# Pi_MCU_shield_2.net
KiCad netlist of a schematic drawn in EAGLE
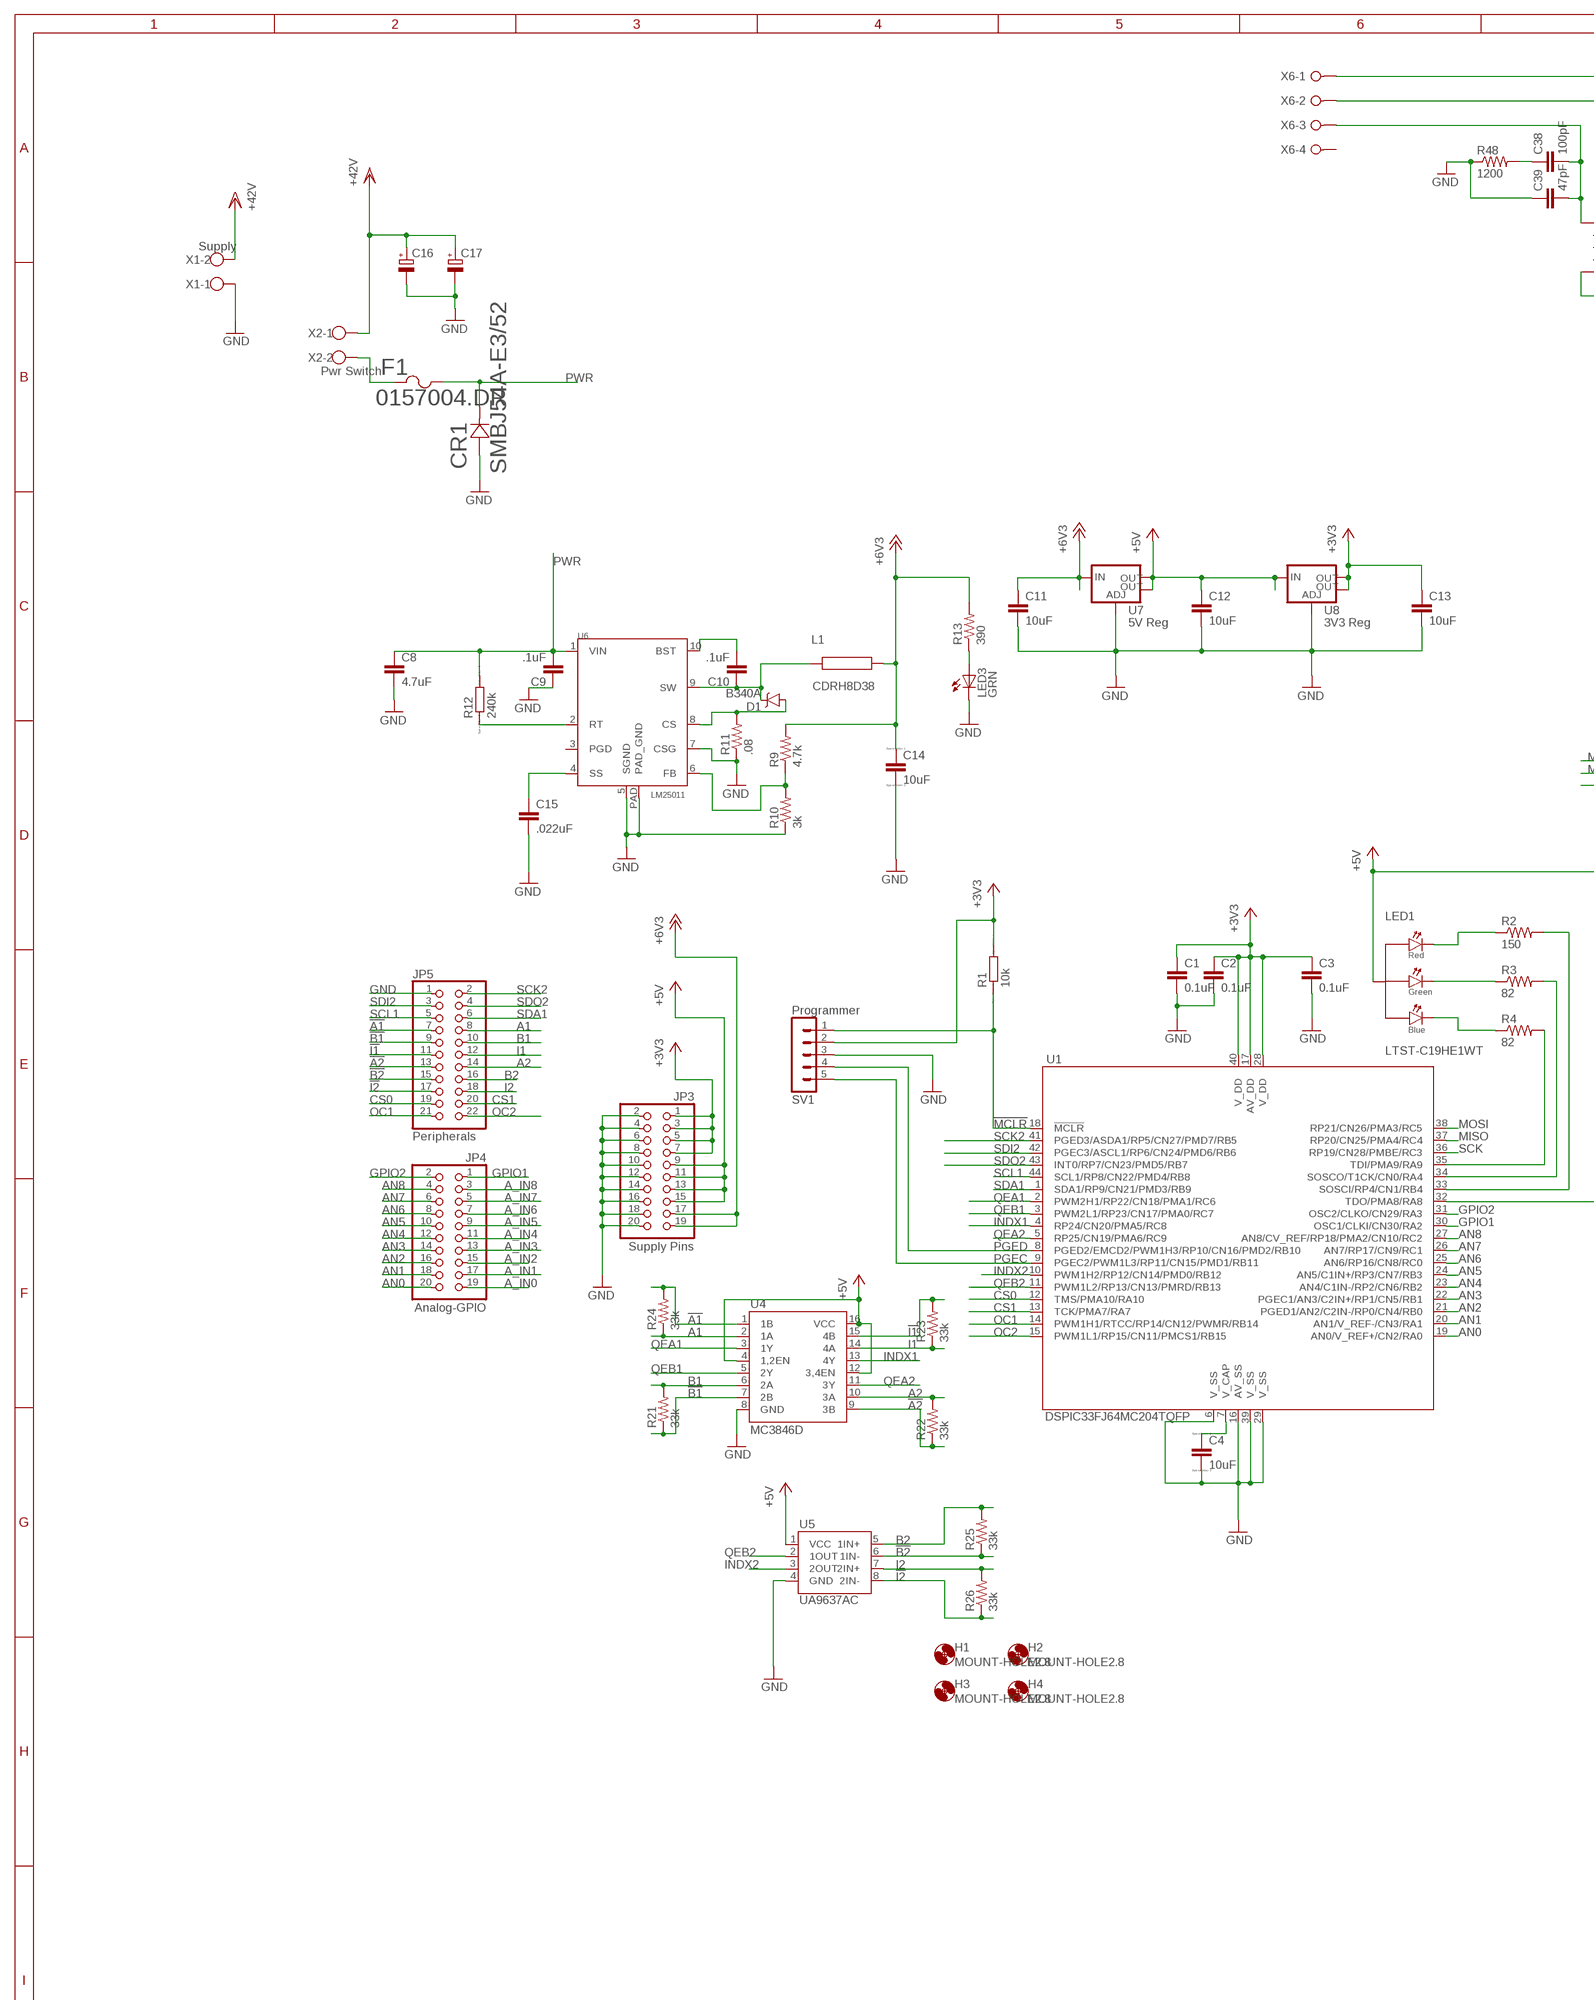
[diagram p0: schematic, sheet 1, part 1 of 2]
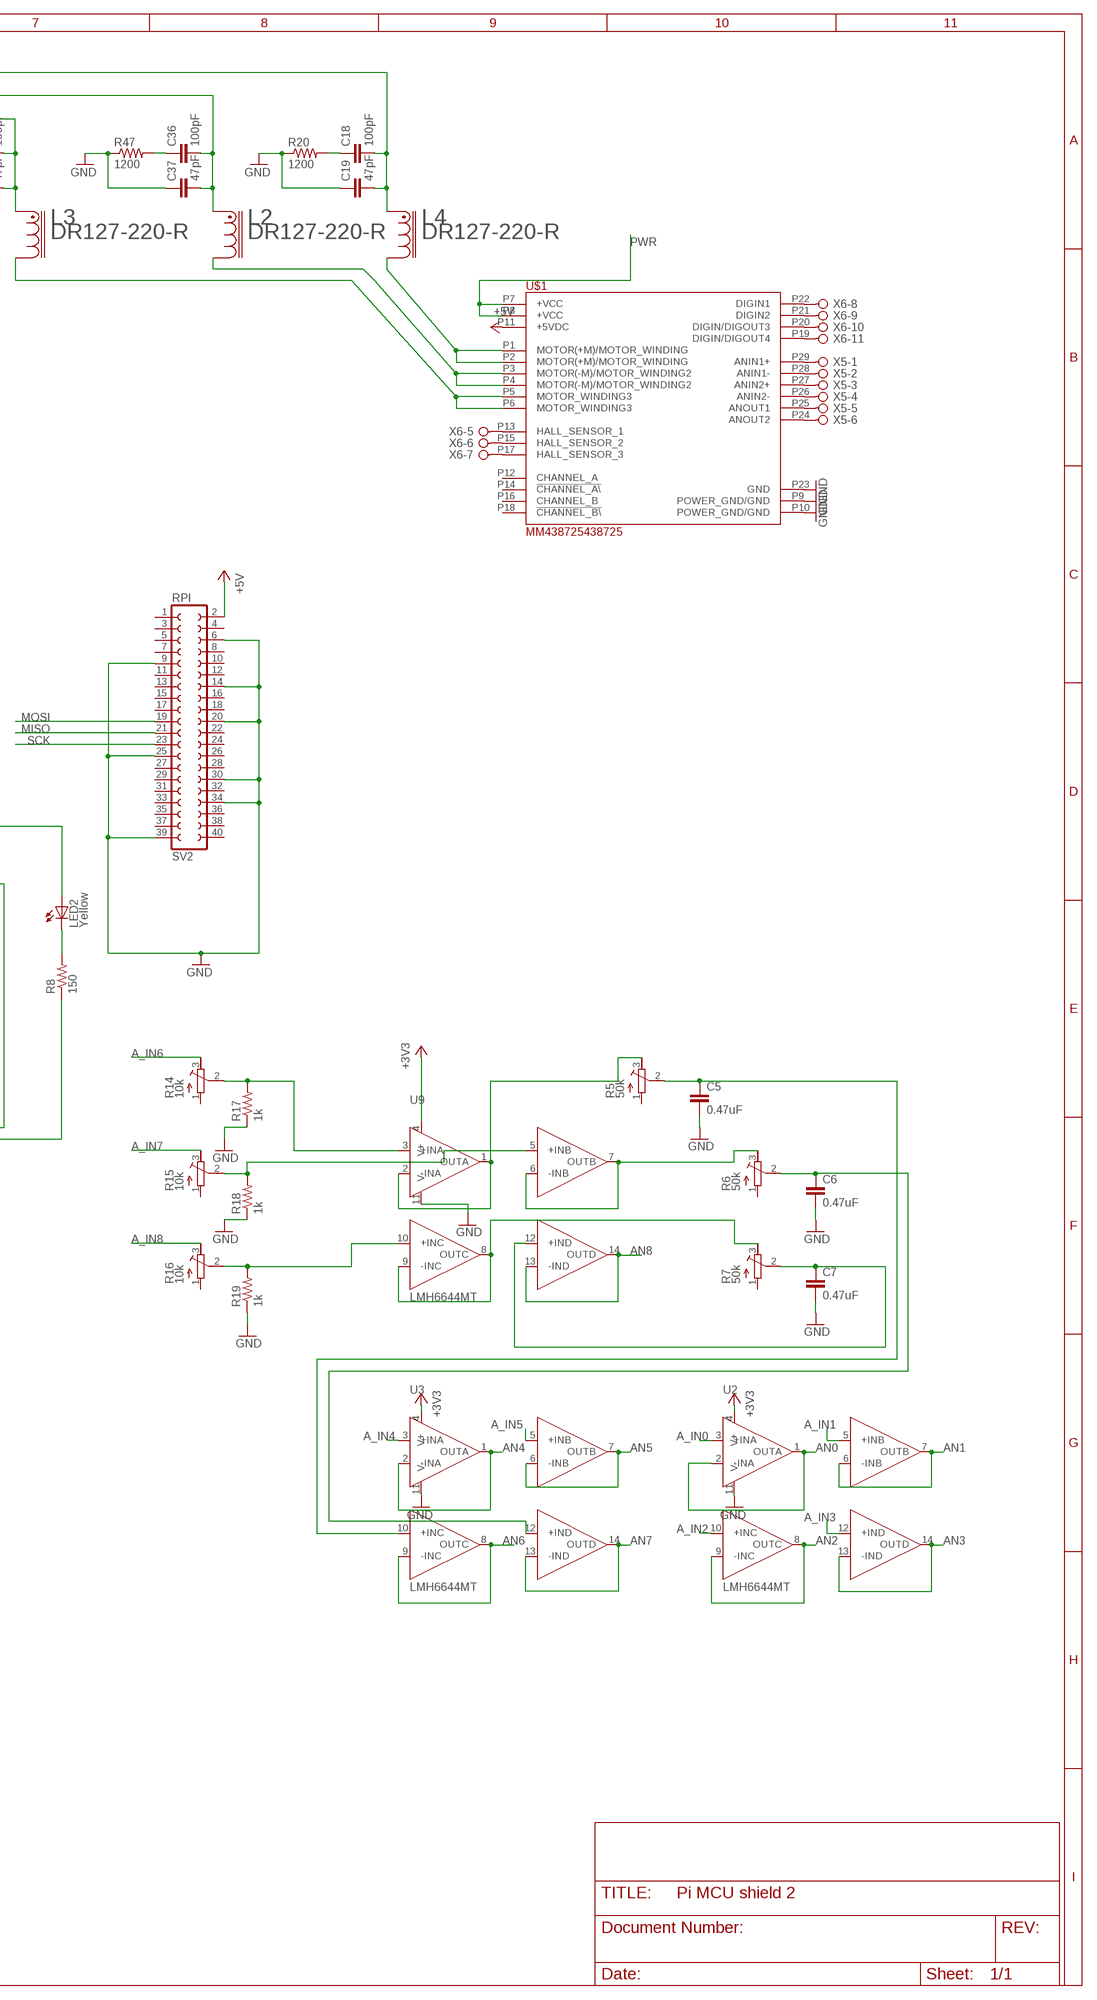
[diagram p1: schematic, sheet 1, part 2 of 2]

(export (version "E")
  (design (tool "Eeschema 10.0.6"))
  (components
    (comp (ref "C1")
      (value "0.1uF")
      (footprint "eagle-import:C0603")
      (libsource (lib "eagle-import") (part "C-EUC0603"))
    )
    (comp (ref "C2")
      (value "0.1uF")
      (footprint "eagle-import:C0603")
      (libsource (lib "eagle-import") (part "C-EUC0603"))
    )
    (comp (ref "C3")
      (value "0.1uF")
      (footprint "eagle-import:C0603")
      (libsource (lib "eagle-import") (part "C-EUC0603"))
    )
    (comp (ref "C4")
      (value "10uF")
      (footprint "eagle-import:C1206")
      (libsource (lib "eagle-import") (part "CC1206"))
    )
    (comp (ref "C5")
      (value "0.47uF")
      (footprint "eagle-import:C0603")
      (libsource (lib "eagle-import") (part "C-EUC0603"))
    )
    (comp (ref "C6")
      (value "0.47uF")
      (footprint "eagle-import:C0603")
      (libsource (lib "eagle-import") (part "C-EUC0603"))
    )
    (comp (ref "C7")
      (value "0.47uF")
      (footprint "eagle-import:C0603")
      (libsource (lib "eagle-import") (part "C-EUC0603"))
    )
    (comp (ref "C8")
      (value "4.7uF")
      (footprint "eagle-import:C1210")
      (libsource (lib "eagle-import") (part "C-EUC1210"))
    )
    (comp (ref "C9")
      (value ".1uF")
      (footprint "eagle-import:0603-CAP")
      (libsource (lib "eagle-import") (part "CAP0603-CAP"))
    )
    (comp (ref "C10")
      (value ".1uF")
      (footprint "eagle-import:0603-CAP")
      (libsource (lib "eagle-import") (part "CAP0603-CAP"))
    )
    (comp (ref "C11")
      (value "10uF")
      (footprint "eagle-import:C0805")
      (libsource (lib "eagle-import") (part "C-EUC0805"))
    )
    (comp (ref "C12")
      (value "10uF")
      (footprint "eagle-import:C0805")
      (libsource (lib "eagle-import") (part "C-EUC0805"))
    )
    (comp (ref "C13")
      (value "10uF")
      (footprint "eagle-import:C0805")
      (libsource (lib "eagle-import") (part "C-EUC0805"))
    )
    (comp (ref "C14")
      (value "10uF")
      (footprint "eagle-import:C1206")
      (libsource (lib "eagle-import") (part "CC1206"))
    )
    (comp (ref "C15")
      (value ".022uF")
      (footprint "eagle-import:0603-CAP")
      (libsource (lib "eagle-import") (part "CAP0603-CAP"))
    )
    (comp (ref "C16")
      (value "CPOL-EUE5-13")
      (footprint "eagle-import:E5-13")
      (libsource (lib "eagle-import") (part "CPOL-EUE5-13"))
    )
    (comp (ref "C17")
      (value "CPOL-EUE5-13")
      (footprint "eagle-import:E5-13")
      (libsource (lib "eagle-import") (part "CPOL-EUE5-13"))
    )
    (comp (ref "C18")
      (value "100pF")
      (footprint "eagle-import:0603-CAP")
      (libsource (lib "eagle-import") (part "CAP0603-CAP"))
    )
    (comp (ref "C19")
      (value "47pF")
      (footprint "eagle-import:0603-CAP")
      (libsource (lib "eagle-import") (part "CAP0603-CAP"))
    )
    (comp (ref "C36")
      (value "100pF")
      (footprint "eagle-import:0603-CAP")
      (libsource (lib "eagle-import") (part "CAP0603-CAP"))
    )
    (comp (ref "C37")
      (value "47pF")
      (footprint "eagle-import:0603-CAP")
      (libsource (lib "eagle-import") (part "CAP0603-CAP"))
    )
    (comp (ref "C38")
      (value "100pF")
      (footprint "eagle-import:0603-CAP")
      (libsource (lib "eagle-import") (part "CAP0603-CAP"))
    )
    (comp (ref "C39")
      (value "47pF")
      (footprint "eagle-import:0603-CAP")
      (libsource (lib "eagle-import") (part "CAP0603-CAP"))
    )
    (comp (ref "CR1")
      (value "SMBJ54A-E3/52")
      (footprint "eagle-import:DIODE_DO-214AC")
      (fields (field (name "MANUFACTURER_PART_NUMBER") "SMBJ54AE352"))
      (libsource (lib "eagle-import") (part "SMBJ54A-E3/52"))
    )
    (comp (ref "D1")
      (value "B340A")
      (footprint "eagle-import:SMA-DIODE")
      (libsource (lib "eagle-import") (part "DIODE-SCHOTTKY-B340A"))
    )
    (comp (ref "F1")
      (value "0157004.DR")
      (footprint "eagle-import:0157SERIES")
      (libsource (lib "eagle-import") (part "0157004.DR"))
    )
    (comp (ref "H1")
      (value "MOUNT-HOLE2.8")
      (footprint "eagle-import:2,8")
      (libsource (lib "eagle-import") (part "MOUNT-HOLE2.8"))
    )
    (comp (ref "H2")
      (value "MOUNT-HOLE2.8")
      (footprint "eagle-import:2,8")
      (libsource (lib "eagle-import") (part "MOUNT-HOLE2.8"))
    )
    (comp (ref "H3")
      (value "MOUNT-HOLE2.8")
      (footprint "eagle-import:2,8")
      (libsource (lib "eagle-import") (part "MOUNT-HOLE2.8"))
    )
    (comp (ref "H4")
      (value "MOUNT-HOLE2.8")
      (footprint "eagle-import:2,8")
      (libsource (lib "eagle-import") (part "MOUNT-HOLE2.8"))
    )
    (comp (ref "JP3")
      (value "Supply Pins")
      (footprint "eagle-import:2X10")
      (libsource (lib "eagle-import") (part "PINHD-2X10"))
    )
    (comp (ref "JP4")
      (value "Analog-GPIO")
      (footprint "eagle-import:2X10")
      (libsource (lib "eagle-import") (part "PINHD-2X10"))
    )
    (comp (ref "JP5")
      (value "Peripherals")
      (footprint "eagle-import:2X11")
      (libsource (lib "eagle-import") (part "PINHD-2X11"))
    )
    (comp (ref "L1")
      (value "CDRH8D38")
      (footprint "eagle-import:CDRH8D38")
      (libsource (lib "eagle-import") (part "CDRH8D38"))
    )
    (comp (ref "L2")
      (value "DR127-220-R")
      (footprint "eagle-import:DR127")
      (fields (field (name "MANUFACTURER_PART_NUMBER") "DR127220R"))
      (libsource (lib "eagle-import") (part "DR127-220-R"))
    )
    (comp (ref "L3")
      (value "DR127-220-R")
      (footprint "eagle-import:DR127")
      (fields (field (name "MANUFACTURER_PART_NUMBER") "DR127220R"))
      (libsource (lib "eagle-import") (part "DR127-220-R"))
    )
    (comp (ref "L4")
      (value "DR127-220-R")
      (footprint "eagle-import:DR127")
      (fields (field (name "MANUFACTURER_PART_NUMBER") "DR127220R"))
      (libsource (lib "eagle-import") (part "DR127-220-R"))
    )
    (comp (ref "LED1")
      (value "LTST-C19HE1WT")
      (footprint "eagle-import:0606")
      (libsource (lib "eagle-import") (part "LTST-C19HE1WT"))
    )
    (comp (ref "LED2")
      (value "Yellow")
      (footprint "eagle-import:SML0603")
      (libsource (lib "eagle-import") (part "LEDSML0603"))
    )
    (comp (ref "LED3")
      (value "GRN")
      (footprint "eagle-import:CHIP-LED0805")
      (libsource (lib "eagle-import") (part "LEDCHIP-LED0805"))
    )
    (comp (ref "R1")
      (value "10k")
      (footprint "eagle-import:R0805")
      (libsource (lib "eagle-import") (part "R"))
    )
    (comp (ref "R2")
      (value "150")
      (footprint "eagle-import:R0603")
      (libsource (lib "eagle-import") (part "R-US_R0603"))
    )
    (comp (ref "R3")
      (value "82")
      (footprint "eagle-import:R0603")
      (libsource (lib "eagle-import") (part "R-US_R0603"))
    )
    (comp (ref "R4")
      (value "82")
      (footprint "eagle-import:R0603")
      (libsource (lib "eagle-import") (part "R-US_R0603"))
    )
    (comp (ref "R5")
      (value "50k")
      (footprint "eagle-import:RTRIM3224J")
      (libsource (lib "eagle-import") (part "R-TRIMM3224J"))
    )
    (comp (ref "R6")
      (value "50k")
      (footprint "eagle-import:RTRIM3224J")
      (libsource (lib "eagle-import") (part "R-TRIMM3224J"))
    )
    (comp (ref "R7")
      (value "50k")
      (footprint "eagle-import:RTRIM3224J")
      (libsource (lib "eagle-import") (part "R-TRIMM3224J"))
    )
    (comp (ref "R8")
      (value "150")
      (footprint "eagle-import:R0603")
      (libsource (lib "eagle-import") (part "R-US_R0603"))
    )
    (comp (ref "R9")
      (value "4.7k")
      (footprint "eagle-import:0603-RES")
      (libsource (lib "eagle-import") (part "RESISTOR0603-RES"))
    )
    (comp (ref "R10")
      (value "3k")
      (footprint "eagle-import:0603-RES")
      (libsource (lib "eagle-import") (part "RESISTOR0603-RES"))
    )
    (comp (ref "R11")
      (value ".08")
      (footprint "eagle-import:0603-RES")
      (libsource (lib "eagle-import") (part "RESISTOR0603-RES"))
    )
    (comp (ref "R12")
      (value "240k")
      (footprint "eagle-import:R0805")
      (libsource (lib "eagle-import") (part "R"))
    )
    (comp (ref "R13")
      (value "390")
      (footprint "eagle-import:0603-RES")
      (libsource (lib "eagle-import") (part "RESISTOR0603-RES"))
    )
    (comp (ref "R14")
      (value "10k")
      (footprint "eagle-import:RTRIM3224J")
      (libsource (lib "eagle-import") (part "R-TRIMM3224J"))
    )
    (comp (ref "R15")
      (value "10k")
      (footprint "eagle-import:RTRIM3224J")
      (libsource (lib "eagle-import") (part "R-TRIMM3224J"))
    )
    (comp (ref "R16")
      (value "10k")
      (footprint "eagle-import:RTRIM3224J")
      (libsource (lib "eagle-import") (part "R-TRIMM3224J"))
    )
    (comp (ref "R17")
      (value "1k")
      (footprint "eagle-import:R0603")
      (libsource (lib "eagle-import") (part "R-US_R0603"))
    )
    (comp (ref "R18")
      (value "1k")
      (footprint "eagle-import:R0603")
      (libsource (lib "eagle-import") (part "R-US_R0603"))
    )
    (comp (ref "R19")
      (value "1k")
      (footprint "eagle-import:R0603")
      (libsource (lib "eagle-import") (part "R-US_R0603"))
    )
    (comp (ref "R20")
      (value "1200")
      (footprint "eagle-import:R0603")
      (libsource (lib "eagle-import") (part "R-US_R0603"))
    )
    (comp (ref "R21")
      (value "33k")
      (footprint "eagle-import:R0603")
      (libsource (lib "eagle-import") (part "R-US_R0603"))
    )
    (comp (ref "R22")
      (value "33k")
      (footprint "eagle-import:R0603")
      (libsource (lib "eagle-import") (part "R-US_R0603"))
    )
    (comp (ref "R23")
      (value "33k")
      (footprint "eagle-import:R0603")
      (libsource (lib "eagle-import") (part "R-US_R0603"))
    )
    (comp (ref "R24")
      (value "33k")
      (footprint "eagle-import:R0603")
      (libsource (lib "eagle-import") (part "R-US_R0603"))
    )
    (comp (ref "R25")
      (value "33k")
      (footprint "eagle-import:R0603")
      (libsource (lib "eagle-import") (part "R-US_R0603"))
    )
    (comp (ref "R26")
      (value "33k")
      (footprint "eagle-import:R0603")
      (libsource (lib "eagle-import") (part "R-US_R0603"))
    )
    (comp (ref "R47")
      (value "1200")
      (footprint "eagle-import:R0603")
      (libsource (lib "eagle-import") (part "R-US_R0603"))
    )
    (comp (ref "R48")
      (value "1200")
      (footprint "eagle-import:R0603")
      (libsource (lib "eagle-import") (part "R-US_R0603"))
    )
    (comp (ref "SV1")
      (value "Programmer")
      (footprint "eagle-import:MA05-1")
      (libsource (lib "eagle-import") (part "MA05-1"))
    )
    (comp (ref "SV2")
      (value "RPI")
      (footprint "eagle-import:FE20-2")
      (libsource (lib "eagle-import") (part "FE20-2"))
    )
    (comp (ref "U$1")
      (value "MM438725438725")
      (footprint "eagle-import:MAX_MOT_438725")
      (libsource (lib "eagle-import") (part "MM438725438725"))
    )
    (comp (ref "U1")
      (value "DSPIC33FJ64MC204TQFP")
      (footprint "eagle-import:TQFP44")
      (libsource (lib "eagle-import") (part "DSPIC33FJ64MC204TQFP"))
    )
    (comp (ref "U2")
      (value "LMH6644MT")
      (footprint "eagle-import:TSSOP14")
      (libsource (lib "eagle-import") (part "LMH6644MT"))
    )
    (comp (ref "U3")
      (value "LMH6644MT")
      (footprint "eagle-import:TSSOP14")
      (libsource (lib "eagle-import") (part "LMH6644MT"))
    )
    (comp (ref "U4")
      (value "MC3846D")
      (footprint "eagle-import:SO-16")
      (libsource (lib "eagle-import") (part "MC3846D"))
    )
    (comp (ref "U5")
      (value "UA9637AC")
      (footprint "eagle-import:SO-08")
      (libsource (lib "eagle-import") (part "UA9637AC"))
    )
    (comp (ref "U6")
      (value "LM25011")
      (footprint "eagle-import:HVSS0P-10")
      (libsource (lib "eagle-import") (part "LM25011"))
    )
    (comp (ref "U7")
      (value "5V Reg")
      (footprint "eagle-import:SOT223")
      (libsource (lib "eagle-import") (part "V_REG_LM1117SOT223"))
    )
    (comp (ref "U8")
      (value "3V3 Reg")
      (footprint "eagle-import:SOT223")
      (libsource (lib "eagle-import") (part "V_REG_LM1117SOT223"))
    )
    (comp (ref "U9")
      (value "LMH6644MT")
      (footprint "eagle-import:TSSOP14")
      (libsource (lib "eagle-import") (part "LMH6644MT"))
    )
    (comp (ref "X1")
      (value "Supply")
      (footprint "eagle-import:W237-102")
      (fields (field (name "MPN") "237-102"))
      (libsource (lib "eagle-import") (part "W237-102"))
    )
    (comp (ref "X2")
      (value "Pwr Switch")
      (footprint "eagle-import:W237-102")
      (fields (field (name "MPN") "237-102"))
      (libsource (lib "eagle-import") (part "W237-102"))
    )
    (comp (ref "X5")
      (value "W237-06P")
      (footprint "eagle-import:W237-6P")
      (libsource (lib "eagle-import") (part "W237-06P"))
    )
    (comp (ref "X6")
      (value "W237-11P")
      (footprint "eagle-import:W237-11P")
      (libsource (lib "eagle-import") (part "W237-11P"))
    )
  )
  (nets
    (net (code "1") (name "+3V3") (class "Default")
      (node (ref "C1") (pin "1") (pinfunction "1_1") (pintype "passive"))
      (node (ref "C13") (pin "1") (pinfunction "1_1") (pintype "passive"))
      (node (ref "C2") (pin "1") (pinfunction "1_1") (pintype "passive"))
      (node (ref "C3") (pin "1") (pinfunction "1_1") (pintype "passive"))
      (node (ref "JP3") (pin "1") (pinfunction "1_1") (pintype "passive"))
      (node (ref "JP3") (pin "3") (pinfunction "3_3") (pintype "passive"))
      (node (ref "JP3") (pin "5") (pinfunction "5_5") (pintype "passive"))
      (node (ref "JP3") (pin "7") (pinfunction "7_7") (pintype "passive"))
      (node (ref "R1") (pin "2") (pinfunction "2_2") (pintype "passive"))
      (node (ref "SV1") (pin "2") (pinfunction "2_2") (pintype "passive"))
      (node (ref "U1") (pin "17") (pinfunction "AV_DD_17") (pintype "power_in"))
      (node (ref "U1") (pin "28") (pinfunction "V_DD_28") (pintype "power_in"))
      (node (ref "U1") (pin "40") (pinfunction "V_DD_40") (pintype "power_in"))
      (node (ref "U2") (pin "4") (pinfunction "V+_4") (pintype "bidirectional"))
      (node (ref "U3") (pin "4") (pinfunction "V+_4") (pintype "bidirectional"))
      (node (ref "U8") (pin "2") (pinfunction "OUT_2") (pintype "output"))
      (node (ref "U8") (pin "4") (pinfunction "OUT_4") (pintype "output"))
      (node (ref "U9") (pin "4") (pinfunction "V+_4") (pintype "bidirectional"))
    )
    (net (code "2") (name "+5V") (class "Default")
      (node (ref "C12") (pin "1") (pinfunction "1_1") (pintype "passive"))
      (node (ref "JP3") (pin "11") (pinfunction "11_11") (pintype "passive"))
      (node (ref "JP3") (pin "13") (pinfunction "13_13") (pintype "passive"))
      (node (ref "JP3") (pin "15") (pinfunction "15_15") (pintype "passive"))
      (node (ref "JP3") (pin "9") (pinfunction "9_9") (pintype "passive"))
      (node (ref "LED1") (pin "4") (pinfunction "ANODE_4") (pintype "passive"))
      (node (ref "LED2") (pin "A") (pinfunction "A_A") (pintype "passive"))
      (node (ref "SV2") (pin "2") (pinfunction "2_2") (pintype "passive"))
      (node (ref "U$1") (pin "P11") (pinfunction "+5VDC_P11") (pintype "power_in"))
      (node (ref "U4") (pin "12") (pinfunction "3,4EN_12") (pintype "bidirectional"))
      (node (ref "U4") (pin "16") (pinfunction "VCC_16") (pintype "power_in"))
      (node (ref "U4") (pin "4") (pinfunction "1,2EN_4") (pintype "input"))
      (node (ref "U5") (pin "1") (pinfunction "VCC_1") (pintype "power_in"))
      (node (ref "U7") (pin "2") (pinfunction "OUT_2") (pintype "output"))
      (node (ref "U7") (pin "4") (pinfunction "OUT_4") (pintype "output"))
      (node (ref "U8") (pin "3") (pinfunction "IN_3") (pintype "input"))
    )
    (net (code "3") (name "+6V3") (class "Default")
      (node (ref "C11") (pin "1") (pinfunction "1_1") (pintype "passive"))
      (node (ref "C14") (pin "1") (pinfunction "1_1") (pintype "passive"))
      (node (ref "JP3") (pin "17") (pinfunction "17_17") (pintype "passive"))
      (node (ref "JP3") (pin "19") (pinfunction "19_19") (pintype "passive"))
      (node (ref "L1") (pin "P$2") (pinfunction "2_P$2") (pintype "passive"))
      (node (ref "R13") (pin "2") (pinfunction "2_2") (pintype "passive"))
      (node (ref "R9") (pin "2") (pinfunction "2_2") (pintype "passive"))
      (node (ref "U7") (pin "3") (pinfunction "IN_3") (pintype "input"))
    )
    (net (code "4") (name "+42V") (class "Default")
      (node (ref "C16") (pin "+") (pinfunction "+_+") (pintype "passive"))
      (node (ref "C17") (pin "+") (pinfunction "+_+") (pintype "passive"))
      (node (ref "X1") (pin "2") (pinfunction "KL_2") (pintype "passive"))
      (node (ref "X2") (pin "1") (pinfunction "KL_1") (pintype "passive"))
    )
    (net (code "5") (name "/A1") (class "Default")
      (node (ref "JP5") (pin "8") (pinfunction "8_8") (pintype "passive"))
      (node (ref "R24") (pin "1") (pinfunction "1_1") (pintype "passive"))
      (node (ref "U4") (pin "2") (pinfunction "1A_2") (pintype "input"))
    )
    (net (code "6") (name "/A2") (class "Default")
      (node (ref "JP5") (pin "14") (pinfunction "14_14") (pintype "passive"))
      (node (ref "R22") (pin "2") (pinfunction "2_2") (pintype "passive"))
      (node (ref "U4") (pin "10") (pinfunction "3A_10") (pintype "input"))
    )
    (net (code "7") (name "/AN0") (class "Default")
      (node (ref "JP4") (pin "20") (pinfunction "20_20") (pintype "passive"))
      (node (ref "U1") (pin "19") (pinfunction "AN0/V_REF+/CN2/RA0_19") (pintype "bidirectional"))
      (node (ref "U2") (pin "1") (pinfunction "OUTA_1") (pintype "bidirectional"))
      (node (ref "U2") (pin "2") (pinfunction "-INA_2") (pintype "bidirectional"))
    )
    (net (code "8") (name "/AN1") (class "Default")
      (node (ref "JP4") (pin "18") (pinfunction "18_18") (pintype "passive"))
      (node (ref "U1") (pin "20") (pinfunction "AN1/V_REF-/CN3/RA1_20") (pintype "bidirectional"))
      (node (ref "U2") (pin "6") (pinfunction "-INB_6") (pintype "bidirectional"))
      (node (ref "U2") (pin "7") (pinfunction "OUTB_7") (pintype "bidirectional"))
    )
    (net (code "9") (name "/AN2") (class "Default")
      (node (ref "JP4") (pin "16") (pinfunction "16_16") (pintype "passive"))
      (node (ref "U1") (pin "21") (pinfunction "PGED1/AN2/C2IN-/RP0/CN4/RB0_21") (pintype "bidirectional"))
      (node (ref "U2") (pin "8") (pinfunction "OUTC_8") (pintype "bidirectional"))
      (node (ref "U2") (pin "9") (pinfunction "-INC_9") (pintype "bidirectional"))
    )
    (net (code "10") (name "/AN3") (class "Default")
      (node (ref "JP4") (pin "14") (pinfunction "14_14") (pintype "passive"))
      (node (ref "U1") (pin "22") (pinfunction "PGEC1/AN3/C2IN+/RP1/CN5/RB1_22") (pintype "bidirectional"))
      (node (ref "U2") (pin "13") (pinfunction "-IND_13") (pintype "bidirectional"))
      (node (ref "U2") (pin "14") (pinfunction "OUTD_14") (pintype "bidirectional"))
    )
    (net (code "11") (name "/AN4") (class "Default")
      (node (ref "JP4") (pin "12") (pinfunction "12_12") (pintype "passive"))
      (node (ref "U1") (pin "23") (pinfunction "AN4/C1IN-/RP2/CN6/RB2_23") (pintype "bidirectional"))
      (node (ref "U3") (pin "1") (pinfunction "OUTA_1") (pintype "bidirectional"))
      (node (ref "U3") (pin "2") (pinfunction "-INA_2") (pintype "bidirectional"))
    )
    (net (code "12") (name "/AN5") (class "Default")
      (node (ref "JP4") (pin "10") (pinfunction "10_10") (pintype "passive"))
      (node (ref "U1") (pin "24") (pinfunction "AN5/C1IN+/RP3/CN7/RB3_24") (pintype "bidirectional"))
      (node (ref "U3") (pin "6") (pinfunction "-INB_6") (pintype "bidirectional"))
      (node (ref "U3") (pin "7") (pinfunction "OUTB_7") (pintype "bidirectional"))
    )
    (net (code "13") (name "/AN6") (class "Default")
      (node (ref "JP4") (pin "8") (pinfunction "8_8") (pintype "passive"))
      (node (ref "U1") (pin "25") (pinfunction "AN6/RP16/CN8/RC0_25") (pintype "bidirectional"))
      (node (ref "U3") (pin "8") (pinfunction "OUTC_8") (pintype "bidirectional"))
      (node (ref "U3") (pin "9") (pinfunction "-INC_9") (pintype "bidirectional"))
    )
    (net (code "14") (name "/AN7") (class "Default")
      (node (ref "JP4") (pin "6") (pinfunction "6_6") (pintype "passive"))
      (node (ref "U1") (pin "26") (pinfunction "AN7/RP17/CN9/RC1_26") (pintype "bidirectional"))
      (node (ref "U3") (pin "13") (pinfunction "-IND_13") (pintype "bidirectional"))
      (node (ref "U3") (pin "14") (pinfunction "OUTD_14") (pintype "bidirectional"))
    )
    (net (code "15") (name "/AN8") (class "Default")
      (node (ref "JP4") (pin "4") (pinfunction "4_4") (pintype "passive"))
      (node (ref "U1") (pin "27") (pinfunction "AN8/CV_REF/RP18/PMA2/CN10/RC2_27") (pintype "bidirectional"))
      (node (ref "U9") (pin "13") (pinfunction "-IND_13") (pintype "bidirectional"))
      (node (ref "U9") (pin "14") (pinfunction "OUTD_14") (pintype "bidirectional"))
    )
    (net (code "16") (name "/A_IN0") (class "Default")
      (node (ref "JP4") (pin "19") (pinfunction "19_19") (pintype "passive"))
      (node (ref "U2") (pin "3") (pinfunction "+INA_3") (pintype "bidirectional"))
    )
    (net (code "17") (name "/A_IN1") (class "Default")
      (node (ref "JP4") (pin "17") (pinfunction "17_17") (pintype "passive"))
      (node (ref "U2") (pin "5") (pinfunction "+INB_5") (pintype "bidirectional"))
    )
    (net (code "18") (name "/A_IN2") (class "Default")
      (node (ref "JP4") (pin "15") (pinfunction "15_15") (pintype "passive"))
      (node (ref "U2") (pin "10") (pinfunction "+INC_10") (pintype "bidirectional"))
    )
    (net (code "19") (name "/A_IN3") (class "Default")
      (node (ref "JP4") (pin "13") (pinfunction "13_13") (pintype "passive"))
      (node (ref "U2") (pin "12") (pinfunction "+IND_12") (pintype "bidirectional"))
    )
    (net (code "20") (name "/A_IN4") (class "Default")
      (node (ref "JP4") (pin "11") (pinfunction "11_11") (pintype "passive"))
      (node (ref "U3") (pin "3") (pinfunction "+INA_3") (pintype "bidirectional"))
    )
    (net (code "21") (name "/A_IN5") (class "Default")
      (node (ref "JP4") (pin "9") (pinfunction "9_9") (pintype "passive"))
      (node (ref "U3") (pin "5") (pinfunction "+INB_5") (pintype "bidirectional"))
    )
    (net (code "22") (name "/A_IN6") (class "Default")
      (node (ref "JP4") (pin "7") (pinfunction "7_7") (pintype "passive"))
      (node (ref "R14") (pin "3") (pinfunction "E_3") (pintype "passive"))
    )
    (net (code "23") (name "/A_IN7") (class "Default")
      (node (ref "JP4") (pin "5") (pinfunction "5_5") (pintype "passive"))
      (node (ref "R15") (pin "3") (pinfunction "E_3") (pintype "passive"))
    )
    (net (code "24") (name "/A_IN8") (class "Default")
      (node (ref "JP4") (pin "3") (pinfunction "3_3") (pintype "passive"))
      (node (ref "R16") (pin "3") (pinfunction "E_3") (pintype "passive"))
    )
    (net (code "25") (name "/B1") (class "Default")
      (node (ref "JP5") (pin "10") (pinfunction "10_10") (pintype "passive"))
      (node (ref "R21") (pin "2") (pinfunction "2_2") (pintype "passive"))
      (node (ref "U4") (pin "6") (pinfunction "2A_6") (pintype "input"))
    )
    (net (code "26") (name "/B2") (class "Default")
      (node (ref "JP5") (pin "16") (pinfunction "16_16") (pintype "passive"))
      (node (ref "R25") (pin "2") (pinfunction "2_2") (pintype "passive"))
      (node (ref "U5") (pin "5") (pinfunction "1IN+_5") (pintype "input"))
    )
    (net (code "27") (name "/CS0") (class "Default")
      (node (ref "JP5") (pin "19") (pinfunction "19_19") (pintype "passive"))
      (node (ref "U1") (pin "12") (pinfunction "TMS/PMA10/RA10_12") (pintype "bidirectional"))
    )
    (net (code "28") (name "/CS1") (class "Default")
      (node (ref "JP5") (pin "20") (pinfunction "20_20") (pintype "passive"))
      (node (ref "U1") (pin "13") (pinfunction "TCK/PMA7/RA7_13") (pintype "bidirectional"))
    )
    (net (code "29") (name "/GPIO1") (class "Default")
      (node (ref "JP4") (pin "1") (pinfunction "1_1") (pintype "passive"))
      (node (ref "U1") (pin "30") (pinfunction "OSC1/CLKI/CN30/RA2_30") (pintype "bidirectional"))
    )
    (net (code "30") (name "/GPIO2") (class "Default")
      (node (ref "JP4") (pin "2") (pinfunction "2_2") (pintype "passive"))
      (node (ref "U1") (pin "31") (pinfunction "OSC2/CLKO/CN29/RA3_31") (pintype "bidirectional"))
    )
    (net (code "31") (name "/I1") (class "Default")
      (node (ref "JP5") (pin "12") (pinfunction "12_12") (pintype "passive"))
      (node (ref "R23") (pin "1") (pinfunction "1_1") (pintype "passive"))
      (node (ref "U4") (pin "14") (pinfunction "4A_14") (pintype "input"))
    )
    (net (code "32") (name "/I2") (class "Default")
      (node (ref "JP5") (pin "18") (pinfunction "18_18") (pintype "passive"))
      (node (ref "R26") (pin "2") (pinfunction "2_2") (pintype "passive"))
      (node (ref "U5") (pin "7") (pinfunction "2IN+_7") (pintype "input"))
    )
    (net (code "33") (name "/INDX1") (class "Default")
      (node (ref "U1") (pin "4") (pinfunction "RP24/CN20/PMA5/RC8_4") (pintype "bidirectional"))
      (node (ref "U4") (pin "13") (pinfunction "4Y_13") (pintype "output"))
    )
    (net (code "34") (name "/INDX2") (class "Default")
      (node (ref "U1") (pin "10") (pinfunction "PWM1H2/RP12/CN14/PMD0/RB12_10") (pintype "bidirectional"))
      (node (ref "U5") (pin "3") (pinfunction "2OUT_3") (pintype "output"))
    )
    (net (code "35") (name "/MISO") (class "Default")
      (node (ref "SV2") (pin "21") (pinfunction "21_21") (pintype "passive"))
      (node (ref "U1") (pin "37") (pinfunction "RP20/CN25/PMA4/RC4_37") (pintype "bidirectional"))
    )
    (net (code "36") (name "/MOSI") (class "Default")
      (node (ref "SV2") (pin "19") (pinfunction "19_19") (pintype "passive"))
      (node (ref "U1") (pin "38") (pinfunction "RP21/CN26/PMA3/RC5_38") (pintype "bidirectional"))
    )
    (net (code "37") (name "/OC1") (class "Default")
      (node (ref "JP5") (pin "21") (pinfunction "21_21") (pintype "passive"))
      (node (ref "U1") (pin "14") (pinfunction "PWM1H1/RTCC/RP14/CN12/PWMR/RB14_14") (pintype "bidirectional"))
    )
    (net (code "38") (name "/OC2") (class "Default")
      (node (ref "JP5") (pin "22") (pinfunction "22_22") (pintype "passive"))
      (node (ref "U1") (pin "15") (pinfunction "PWM1L1/RP15/CN11/PMCS1/RB15_15") (pintype "bidirectional"))
    )
    (net (code "39") (name "/PGEC") (class "Default")
      (node (ref "SV1") (pin "5") (pinfunction "5_5") (pintype "passive"))
      (node (ref "U1") (pin "9") (pinfunction "PGEC2/PWM1L3/RP11/CN15/PMD1/RB11_9") (pintype "bidirectional"))
    )
    (net (code "40") (name "/PGED") (class "Default")
      (node (ref "SV1") (pin "4") (pinfunction "4_4") (pintype "passive"))
      (node (ref "U1") (pin "8") (pinfunction "PGED2/EMCD2/PWM1H3/RP10/CN16/PMD2/RB10_8") (pintype "bidirectional"))
    )
    (net (code "41") (name "/PWR") (class "Default")
      (node (ref "C8") (pin "1") (pinfunction "1_1") (pintype "passive"))
      (node (ref "C9") (pin "2") (pinfunction "2_2") (pintype "passive"))
      (node (ref "CR1") (pin "1") (pinfunction "12_1") (pintype "passive"))
      (node (ref "F1") (pin "2") (pinfunction "2_2") (pintype "passive"))
      (node (ref "R12") (pin "2") (pinfunction "2_2") (pintype "passive"))
      (node (ref "U$1") (pin "P7") (pinfunction "+VCC_P7") (pintype "power_in"))
      (node (ref "U$1") (pin "P8") (pinfunction "+VCC_P8") (pintype "power_in"))
      (node (ref "U6") (pin "1") (pinfunction "VIN_1") (pintype "bidirectional"))
    )
    (net (code "42") (name "/QEA1") (class "Default")
      (node (ref "U1") (pin "2") (pinfunction "PWM2H1/RP22/CN18/PMA1/RC6_2") (pintype "bidirectional"))
      (node (ref "U4") (pin "3") (pinfunction "1Y_3") (pintype "output"))
    )
    (net (code "43") (name "/QEA2") (class "Default")
      (node (ref "U1") (pin "5") (pinfunction "RP25/CN19/PMA6/RC9_5") (pintype "bidirectional"))
      (node (ref "U4") (pin "11") (pinfunction "3Y_11") (pintype "output"))
    )
    (net (code "44") (name "/QEB1") (class "Default")
      (node (ref "U1") (pin "3") (pinfunction "PWM2L1/RP23/CN17/PMA0/RC7_3") (pintype "bidirectional"))
      (node (ref "U4") (pin "5") (pinfunction "2Y_5") (pintype "output"))
    )
    (net (code "45") (name "/QEB2") (class "Default")
      (node (ref "U1") (pin "11") (pinfunction "PWM1L2/RP13/CN13/PMRD/RB13_11") (pintype "bidirectional"))
      (node (ref "U5") (pin "2") (pinfunction "1OUT_2") (pintype "output"))
    )
    (net (code "46") (name "/SCK") (class "Default")
      (node (ref "SV2") (pin "23") (pinfunction "23_23") (pintype "passive"))
      (node (ref "U1") (pin "36") (pinfunction "RP19/CN28/PMBE/RC3_36") (pintype "bidirectional"))
    )
    (net (code "47") (name "/SCK2") (class "Default")
      (node (ref "JP5") (pin "2") (pinfunction "2_2") (pintype "passive"))
      (node (ref "U1") (pin "41") (pinfunction "PGED3/ASDA1/RP5/CN27/PMD7/RB5_41") (pintype "bidirectional"))
    )
    (net (code "48") (name "/SCL1") (class "Default")
      (node (ref "JP5") (pin "5") (pinfunction "5_5") (pintype "passive"))
      (node (ref "U1") (pin "44") (pinfunction "SCL1/RP8/CN22/PMD4/RB8_44") (pintype "bidirectional"))
    )
    (net (code "49") (name "/SDA1") (class "Default")
      (node (ref "JP5") (pin "6") (pinfunction "6_6") (pintype "passive"))
      (node (ref "U1") (pin "1") (pinfunction "SDA1/RP9/CN21/PMD3/RB9_1") (pintype "bidirectional"))
    )
    (net (code "50") (name "/SDI2") (class "Default")
      (node (ref "JP5") (pin "3") (pinfunction "3_3") (pintype "passive"))
      (node (ref "U1") (pin "42") (pinfunction "PGEC3/ASCL1/RP6/CN24/PMD6/RB6_42") (pintype "bidirectional"))
    )
    (net (code "51") (name "/SDO2") (class "Default")
      (node (ref "JP5") (pin "4") (pinfunction "4_4") (pintype "passive"))
      (node (ref "U1") (pin "43") (pinfunction "INT0/RP7/CN23/PMD5/RB7_43") (pintype "bidirectional"))
    )
    (net (code "52") (name "/~{A1}") (class "Default")
      (node (ref "JP5") (pin "7") (pinfunction "7_7") (pintype "passive"))
      (node (ref "R24") (pin "2") (pinfunction "2_2") (pintype "passive"))
      (node (ref "U4") (pin "1") (pinfunction "1B_1") (pintype "input"))
    )
    (net (code "53") (name "/~{A2}") (class "Default")
      (node (ref "JP5") (pin "13") (pinfunction "13_13") (pintype "passive"))
      (node (ref "R22") (pin "1") (pinfunction "1_1") (pintype "passive"))
      (node (ref "U4") (pin "9") (pinfunction "3B_9") (pintype "input"))
    )
    (net (code "54") (name "/~{B1}") (class "Default")
      (node (ref "JP5") (pin "9") (pinfunction "9_9") (pintype "passive"))
      (node (ref "R21") (pin "1") (pinfunction "1_1") (pintype "passive"))
      (node (ref "U4") (pin "7") (pinfunction "2B_7") (pintype "input"))
    )
    (net (code "55") (name "/~{B2}") (class "Default")
      (node (ref "JP5") (pin "15") (pinfunction "15_15") (pintype "passive"))
      (node (ref "R25") (pin "1") (pinfunction "1_1") (pintype "passive"))
      (node (ref "U5") (pin "6") (pinfunction "1IN-_6") (pintype "input"))
    )
    (net (code "56") (name "/~{I1}") (class "Default")
      (node (ref "JP5") (pin "11") (pinfunction "11_11") (pintype "passive"))
      (node (ref "R23") (pin "2") (pinfunction "2_2") (pintype "passive"))
      (node (ref "U4") (pin "15") (pinfunction "4B_15") (pintype "input"))
    )
    (net (code "57") (name "/~{I2}") (class "Default")
      (node (ref "JP5") (pin "17") (pinfunction "17_17") (pintype "passive"))
      (node (ref "R26") (pin "1") (pinfunction "1_1") (pintype "passive"))
      (node (ref "U5") (pin "8") (pinfunction "2IN-_8") (pintype "input"))
    )
    (net (code "58") (name "/~{MCLR}") (class "Default")
      (node (ref "R1") (pin "1") (pinfunction "1_1") (pintype "passive"))
      (node (ref "SV1") (pin "1") (pinfunction "1_1") (pintype "passive"))
      (node (ref "U1") (pin "18") (pinfunction "~{MCLR}_18") (pintype "bidirectional"))
    )
    (net (code "59") (name "GND") (class "Default")
      (node (ref "C1") (pin "2") (pinfunction "2_2") (pintype "passive"))
      (node (ref "C11") (pin "2") (pinfunction "2_2") (pintype "passive"))
      (node (ref "C12") (pin "2") (pinfunction "2_2") (pintype "passive"))
      (node (ref "C13") (pin "2") (pinfunction "2_2") (pintype "passive"))
      (node (ref "C14") (pin "2") (pinfunction "2_2") (pintype "passive"))
      (node (ref "C15") (pin "2") (pinfunction "2_2") (pintype "passive"))
      (node (ref "C16") (pin "-") (pinfunction "-_-") (pintype "passive"))
      (node (ref "C17") (pin "-") (pinfunction "-_-") (pintype "passive"))
      (node (ref "C19") (pin "1") (pinfunction "1_1") (pintype "passive"))
      (node (ref "C2") (pin "2") (pinfunction "2_2") (pintype "passive"))
      (node (ref "C3") (pin "2") (pinfunction "2_2") (pintype "passive"))
      (node (ref "C37") (pin "1") (pinfunction "1_1") (pintype "passive"))
      (node (ref "C39") (pin "1") (pinfunction "1_1") (pintype "passive"))
      (node (ref "C4") (pin "2") (pinfunction "2_2") (pintype "passive"))
      (node (ref "C5") (pin "2") (pinfunction "2_2") (pintype "passive"))
      (node (ref "C6") (pin "2") (pinfunction "2_2") (pintype "passive"))
      (node (ref "C7") (pin "2") (pinfunction "2_2") (pintype "passive"))
      (node (ref "C8") (pin "2") (pinfunction "2_2") (pintype "passive"))
      (node (ref "C9") (pin "1") (pinfunction "1_1") (pintype "passive"))
      (node (ref "CR1") (pin "2") (pinfunction "21_2") (pintype "passive"))
      (node (ref "JP3") (pin "10") (pinfunction "10_10") (pintype "passive"))
      (node (ref "JP3") (pin "12") (pinfunction "12_12") (pintype "passive"))
      (node (ref "JP3") (pin "14") (pinfunction "14_14") (pintype "passive"))
      (node (ref "JP3") (pin "16") (pinfunction "16_16") (pintype "passive"))
      (node (ref "JP3") (pin "18") (pinfunction "18_18") (pintype "passive"))
      (node (ref "JP3") (pin "2") (pinfunction "2_2") (pintype "passive"))
      (node (ref "JP3") (pin "20") (pinfunction "20_20") (pintype "passive"))
      (node (ref "JP3") (pin "4") (pinfunction "4_4") (pintype "passive"))
      (node (ref "JP3") (pin "6") (pinfunction "6_6") (pintype "passive"))
      (node (ref "JP3") (pin "8") (pinfunction "8_8") (pintype "passive"))
      (node (ref "JP5") (pin "1") (pinfunction "1_1") (pintype "passive"))
      (node (ref "LED3") (pin "C") (pinfunction "C_C") (pintype "passive"))
      (node (ref "R10") (pin "1") (pinfunction "1_1") (pintype "passive"))
      (node (ref "R11") (pin "1") (pinfunction "1_1") (pintype "passive"))
      (node (ref "R17") (pin "1") (pinfunction "1_1") (pintype "passive"))
      (node (ref "R18") (pin "1") (pinfunction "1_1") (pintype "passive"))
      (node (ref "R19") (pin "1") (pinfunction "1_1") (pintype "passive"))
      (node (ref "R20") (pin "1") (pinfunction "1_1") (pintype "passive"))
      (node (ref "R47") (pin "1") (pinfunction "1_1") (pintype "passive"))
      (node (ref "R48") (pin "1") (pinfunction "1_1") (pintype "passive"))
      (node (ref "SV1") (pin "3") (pinfunction "3_3") (pintype "passive"))
      (node (ref "SV2") (pin "14") (pinfunction "14_14") (pintype "passive"))
      (node (ref "SV2") (pin "20") (pinfunction "20_20") (pintype "passive"))
      (node (ref "SV2") (pin "25") (pinfunction "25_25") (pintype "passive"))
      (node (ref "SV2") (pin "30") (pinfunction "30_30") (pintype "passive"))
      (node (ref "SV2") (pin "34") (pinfunction "34_34") (pintype "passive"))
      (node (ref "SV2") (pin "39") (pinfunction "39_39") (pintype "passive"))
      (node (ref "SV2") (pin "6") (pinfunction "6_6") (pintype "passive"))
      (node (ref "SV2") (pin "9") (pinfunction "9_9") (pintype "passive"))
      (node (ref "U$1") (pin "P10") (pinfunction "POWER_GND/GND_P10") (pintype "power_in"))
      (node (ref "U$1") (pin "P23") (pinfunction "GND_P23") (pintype "power_in"))
      (node (ref "U$1") (pin "P9") (pinfunction "POWER_GND/GND_P9") (pintype "power_in"))
      (node (ref "U1") (pin "16") (pinfunction "AV_SS_16") (pintype "power_in"))
      (node (ref "U1") (pin "29") (pinfunction "V_SS_29") (pintype "power_in"))
      (node (ref "U1") (pin "39") (pinfunction "V_SS_39") (pintype "power_in"))
      (node (ref "U1") (pin "6") (pinfunction "V_SS_6") (pintype "power_in"))
      (node (ref "U2") (pin "11") (pinfunction "V-_11") (pintype "bidirectional"))
      (node (ref "U3") (pin "11") (pinfunction "V-_11") (pintype "bidirectional"))
      (node (ref "U4") (pin "8") (pinfunction "GND_8") (pintype "power_in"))
      (node (ref "U5") (pin "4") (pinfunction "GND_4") (pintype "power_in"))
      (node (ref "U6") (pin "5") (pinfunction "SGND_5") (pintype "bidirectional"))
      (node (ref "U6") (pin "7") (pinfunction "CSG_7") (pintype "bidirectional"))
      (node (ref "U6") (pin "PAD") (pinfunction "PAD_GND_PAD") (pintype "bidirectional"))
      (node (ref "U7") (pin "1") (pinfunction "ADJ_1") (pintype "input"))
      (node (ref "U8") (pin "1") (pinfunction "ADJ_1") (pintype "input"))
      (node (ref "U9") (pin "11") (pinfunction "V-_11") (pintype "bidirectional"))
      (node (ref "X1") (pin "1") (pinfunction "KL_1") (pintype "passive"))
    )
    (net (code "60") (name "Net-(C18-Pad1)") (class "Default")
      (node (ref "C18") (pin "1") (pinfunction "1_1") (pintype "passive"))
      (node (ref "R20") (pin "2") (pinfunction "2_2") (pintype "passive"))
    )
    (net (code "61") (name "Net-(C36-Pad1)") (class "Default")
      (node (ref "C36") (pin "1") (pinfunction "1_1") (pintype "passive"))
      (node (ref "R47") (pin "2") (pinfunction "2_2") (pintype "passive"))
    )
    (net (code "62") (name "Net-(C38-Pad1)") (class "Default")
      (node (ref "C38") (pin "1") (pinfunction "1_1") (pintype "passive"))
      (node (ref "R48") (pin "2") (pinfunction "2_2") (pintype "passive"))
    )
    (net (code "63") (name "Net-(L1-1)") (class "Default")
      (node (ref "C10") (pin "1") (pinfunction "1_1") (pintype "passive"))
      (node (ref "D1") (pin "C") (pinfunction "C_C") (pintype "passive"))
      (node (ref "L1") (pin "P$1") (pinfunction "1_P$1") (pintype "passive"))
      (node (ref "U6") (pin "9") (pinfunction "SW_9") (pintype "bidirectional"))
    )
    (net (code "64") (name "Net-(L2-Pad2)") (class "Default")
      (node (ref "L2") (pin "2") (pinfunction "2_2") (pintype "passive"))
      (node (ref "U$1") (pin "P3") (pinfunction "MOTOR(-M)/MOTOR_WINDING2_P3") (pintype "bidirectional"))
      (node (ref "U$1") (pin "P4") (pinfunction "MOTOR(-M)/MOTOR_WINDING2_P4") (pintype "bidirectional"))
    )
    (net (code "65") (name "Net-(L3-Pad2)") (class "Default")
      (node (ref "L3") (pin "2") (pinfunction "2_2") (pintype "passive"))
      (node (ref "U$1") (pin "P5") (pinfunction "MOTOR_WINDING3_P5") (pintype "bidirectional"))
      (node (ref "U$1") (pin "P6") (pinfunction "MOTOR_WINDING3_P6") (pintype "bidirectional"))
    )
    (net (code "66") (name "Net-(L4-Pad2)") (class "Default")
      (node (ref "L4") (pin "2") (pinfunction "2_2") (pintype "passive"))
      (node (ref "U$1") (pin "P1") (pinfunction "MOTOR(+M)/MOTOR_WINDING_P1") (pintype "bidirectional"))
      (node (ref "U$1") (pin "P2") (pinfunction "MOTOR(+M)/MOTOR_WINDING_P2") (pintype "bidirectional"))
    )
    (net (code "67") (name "Net-(LED1-B_CATHODE)") (class "Default")
      (node (ref "LED1") (pin "3") (pinfunction "B_CATHODE_3") (pintype "passive"))
      (node (ref "R4") (pin "1") (pinfunction "1_1") (pintype "passive"))
    )
    (net (code "68") (name "Net-(LED1-G_CATHODE)") (class "Default")
      (node (ref "LED1") (pin "2") (pinfunction "G_CATHODE_2") (pintype "passive"))
      (node (ref "R3") (pin "1") (pinfunction "1_1") (pintype "passive"))
    )
    (net (code "69") (name "Net-(LED1-R_CATHODE)") (class "Default")
      (node (ref "LED1") (pin "1") (pinfunction "R_CATHODE_1") (pintype "passive"))
      (node (ref "R2") (pin "1") (pinfunction "1_1") (pintype "passive"))
    )
    (net (code "70") (name "Net-(LED2-PadC)") (class "Default")
      (node (ref "LED2") (pin "C") (pinfunction "C_C") (pintype "passive"))
      (node (ref "R8") (pin "2") (pinfunction "2_2") (pintype "passive"))
    )
    (net (code "71") (name "Net-(LED3-PadA)") (class "Default")
      (node (ref "LED3") (pin "A") (pinfunction "A_A") (pintype "passive"))
      (node (ref "R13") (pin "1") (pinfunction "1_1") (pintype "passive"))
    )
    (net (code "72") (name "Net-(R5-E)") (class "Default")
      (node (ref "R5") (pin "3") (pinfunction "E_3") (pintype "passive"))
      (node (ref "U9") (pin "1") (pinfunction "OUTA_1") (pintype "bidirectional"))
      (node (ref "U9") (pin "2") (pinfunction "-INA_2") (pintype "bidirectional"))
    )
    (net (code "73") (name "Net-(R5-S)") (class "Default")
      (node (ref "C5") (pin "1") (pinfunction "1_1") (pintype "passive"))
      (node (ref "R5") (pin "2") (pinfunction "S_2") (pintype "passive"))
      (node (ref "U3") (pin "10") (pinfunction "+INC_10") (pintype "bidirectional"))
    )
    (net (code "74") (name "Net-(R6-E)") (class "Default")
      (node (ref "R6") (pin "3") (pinfunction "E_3") (pintype "passive"))
      (node (ref "U9") (pin "6") (pinfunction "-INB_6") (pintype "bidirectional"))
      (node (ref "U9") (pin "7") (pinfunction "OUTB_7") (pintype "bidirectional"))
    )
    (net (code "75") (name "Net-(R6-S)") (class "Default")
      (node (ref "C6") (pin "1") (pinfunction "1_1") (pintype "passive"))
      (node (ref "R6") (pin "2") (pinfunction "S_2") (pintype "passive"))
      (node (ref "U3") (pin "12") (pinfunction "+IND_12") (pintype "bidirectional"))
    )
    (net (code "76") (name "Net-(R7-E)") (class "Default")
      (node (ref "R7") (pin "3") (pinfunction "E_3") (pintype "passive"))
      (node (ref "U9") (pin "8") (pinfunction "OUTC_8") (pintype "bidirectional"))
      (node (ref "U9") (pin "9") (pinfunction "-INC_9") (pintype "bidirectional"))
    )
    (net (code "77") (name "Net-(R7-S)") (class "Default")
      (node (ref "C7") (pin "1") (pinfunction "1_1") (pintype "passive"))
      (node (ref "R7") (pin "2") (pinfunction "S_2") (pintype "passive"))
      (node (ref "U9") (pin "12") (pinfunction "+IND_12") (pintype "bidirectional"))
    )
    (net (code "78") (name "Net-(R14-S)") (class "Default")
      (node (ref "R14") (pin "2") (pinfunction "S_2") (pintype "passive"))
      (node (ref "R17") (pin "2") (pinfunction "2_2") (pintype "passive"))
      (node (ref "U9") (pin "3") (pinfunction "+INA_3") (pintype "bidirectional"))
    )
    (net (code "79") (name "Net-(R15-S)") (class "Default")
      (node (ref "R15") (pin "2") (pinfunction "S_2") (pintype "passive"))
      (node (ref "R18") (pin "2") (pinfunction "2_2") (pintype "passive"))
      (node (ref "U9") (pin "5") (pinfunction "+INB_5") (pintype "bidirectional"))
    )
    (net (code "80") (name "Net-(R16-S)") (class "Default")
      (node (ref "R16") (pin "2") (pinfunction "S_2") (pintype "passive"))
      (node (ref "R19") (pin "2") (pinfunction "2_2") (pintype "passive"))
      (node (ref "U9") (pin "10") (pinfunction "+INC_10") (pintype "bidirectional"))
    )
    (net (code "81") (name "Net-(U$1-ANIN1+)") (class "Default")
      (node (ref "U$1") (pin "P29") (pinfunction "ANIN1+_P29") (pintype "input"))
      (node (ref "X5") (pin "1") (pinfunction "KL_1") (pintype "passive"))
    )
    (net (code "82") (name "Net-(U$1-ANIN1-)") (class "Default")
      (node (ref "U$1") (pin "P28") (pinfunction "ANIN1-_P28") (pintype "input"))
      (node (ref "X5") (pin "2") (pinfunction "KL_2") (pintype "passive"))
    )
    (net (code "83") (name "Net-(U$1-ANIN2+)") (class "Default")
      (node (ref "U$1") (pin "P27") (pinfunction "ANIN2+_P27") (pintype "input"))
      (node (ref "X5") (pin "3") (pinfunction "KL_3") (pintype "passive"))
    )
    (net (code "84") (name "Net-(U$1-ANIN2-)") (class "Default")
      (node (ref "U$1") (pin "P26") (pinfunction "ANIN2-_P26") (pintype "input"))
      (node (ref "X5") (pin "4") (pinfunction "KL_4") (pintype "passive"))
    )
    (net (code "85") (name "Net-(U$1-ANOUT1)") (class "Default")
      (node (ref "U$1") (pin "P25") (pinfunction "ANOUT1_P25") (pintype "output"))
      (node (ref "X5") (pin "5") (pinfunction "KL_5") (pintype "passive"))
    )
    (net (code "86") (name "Net-(U$1-ANOUT2)") (class "Default")
      (node (ref "U$1") (pin "P24") (pinfunction "ANOUT2_P24") (pintype "output"))
      (node (ref "X5") (pin "6") (pinfunction "KL_6") (pintype "passive"))
    )
    (net (code "87") (name "Net-(U$1-DIGIN1)") (class "Default")
      (node (ref "U$1") (pin "P22") (pinfunction "DIGIN1_P22") (pintype "input"))
      (node (ref "X6") (pin "8") (pinfunction "KL_8") (pintype "passive"))
    )
    (net (code "88") (name "Net-(U$1-DIGIN2)") (class "Default")
      (node (ref "U$1") (pin "P21") (pinfunction "DIGIN2_P21") (pintype "input"))
      (node (ref "X6") (pin "9") (pinfunction "KL_9") (pintype "passive"))
    )
    (net (code "89") (name "Net-(U$1-DIGIN{slash}DIGOUT3)") (class "Default")
      (node (ref "U$1") (pin "P20") (pinfunction "DIGIN/DIGOUT3_P20") (pintype "bidirectional"))
      (node (ref "X6") (pin "10") (pinfunction "KL_10") (pintype "passive"))
    )
    (net (code "90") (name "Net-(U$1-DIGIN{slash}DIGOUT4)") (class "Default")
      (node (ref "U$1") (pin "P19") (pinfunction "DIGIN/DIGOUT4_P19") (pintype "bidirectional"))
      (node (ref "X6") (pin "11") (pinfunction "KL_11") (pintype "passive"))
    )
    (net (code "91") (name "Net-(U$1-HALL_SENSOR_1)") (class "Default")
      (node (ref "U$1") (pin "P13") (pinfunction "HALL_SENSOR_1_P13") (pintype "input"))
      (node (ref "X6") (pin "5") (pinfunction "KL_5") (pintype "passive"))
    )
    (net (code "92") (name "Net-(U$1-HALL_SENSOR_2)") (class "Default")
      (node (ref "U$1") (pin "P15") (pinfunction "HALL_SENSOR_2_P15") (pintype "input"))
      (node (ref "X6") (pin "6") (pinfunction "KL_6") (pintype "passive"))
    )
    (net (code "93") (name "Net-(U$1-HALL_SENSOR_3)") (class "Default")
      (node (ref "U$1") (pin "P17") (pinfunction "HALL_SENSOR_3_P17") (pintype "input"))
      (node (ref "X6") (pin "7") (pinfunction "KL_7") (pintype "passive"))
    )
    (net (code "94") (name "Net-(U1-SOSCI{slash}RP4{slash}CN1{slash}RB4)") (class "Default")
      (node (ref "R2") (pin "2") (pinfunction "2_2") (pintype "passive"))
      (node (ref "U1") (pin "33") (pinfunction "SOSCI/RP4/CN1/RB4_33") (pintype "bidirectional"))
    )
    (net (code "95") (name "Net-(U1-SOSCO{slash}T1CK{slash}CN0{slash}RA4)") (class "Default")
      (node (ref "R3") (pin "2") (pinfunction "2_2") (pintype "passive"))
      (node (ref "U1") (pin "34") (pinfunction "SOSCO/T1CK/CN0/RA4_34") (pintype "bidirectional"))
    )
    (net (code "96") (name "Net-(U1-TDI{slash}PMA9{slash}RA9)") (class "Default")
      (node (ref "R4") (pin "2") (pinfunction "2_2") (pintype "passive"))
      (node (ref "U1") (pin "35") (pinfunction "TDI/PMA9/RA9_35") (pintype "bidirectional"))
    )
    (net (code "97") (name "Net-(U1-TDO{slash}PMA8{slash}RA8)") (class "Default")
      (node (ref "R8") (pin "1") (pinfunction "1_1") (pintype "passive"))
      (node (ref "U1") (pin "32") (pinfunction "TDO/PMA8/RA8_32") (pintype "bidirectional"))
    )
    (net (code "98") (name "Net-(U1-V_CAP)") (class "Default")
      (node (ref "C4") (pin "1") (pinfunction "1_1") (pintype "passive"))
      (node (ref "U1") (pin "7") (pinfunction "V_CAP_7") (pintype "power_in"))
    )
    (net (code "99") (name "Net-(U6-BST)") (class "Default")
      (node (ref "C10") (pin "2") (pinfunction "2_2") (pintype "passive"))
      (node (ref "U6") (pin "10") (pinfunction "BST_10") (pintype "bidirectional"))
    )
    (net (code "100") (name "Net-(U6-CS)") (class "Default")
      (node (ref "D1") (pin "A") (pinfunction "A_A") (pintype "passive"))
      (node (ref "R11") (pin "2") (pinfunction "2_2") (pintype "passive"))
      (node (ref "U6") (pin "8") (pinfunction "CS_8") (pintype "bidirectional"))
    )
    (net (code "101") (name "Net-(U6-FB)") (class "Default")
      (node (ref "R10") (pin "2") (pinfunction "2_2") (pintype "passive"))
      (node (ref "R9") (pin "1") (pinfunction "1_1") (pintype "passive"))
      (node (ref "U6") (pin "6") (pinfunction "FB_6") (pintype "bidirectional"))
    )
    (net (code "102") (name "Net-(U6-RT)") (class "Default")
      (node (ref "R12") (pin "1") (pinfunction "1_1") (pintype "passive"))
      (node (ref "U6") (pin "2") (pinfunction "RT_2") (pintype "bidirectional"))
    )
    (net (code "103") (name "Net-(U6-SS)") (class "Default")
      (node (ref "C15") (pin "1") (pinfunction "1_1") (pintype "passive"))
      (node (ref "U6") (pin "4") (pinfunction "SS_4") (pintype "bidirectional"))
    )
    (net (code "104") (name "Net-(X2B-KL)") (class "Default")
      (node (ref "F1") (pin "1") (pinfunction "1_1") (pintype "passive"))
      (node (ref "X2") (pin "2") (pinfunction "KL_2") (pintype "passive"))
    )
    (net (code "105") (name "Net-(X6A-KL)") (class "Default")
      (node (ref "C18") (pin "2") (pinfunction "2_2") (pintype "passive"))
      (node (ref "C19") (pin "2") (pinfunction "2_2") (pintype "passive"))
      (node (ref "L4") (pin "1") (pinfunction "1_1") (pintype "passive"))
      (node (ref "X6") (pin "1") (pinfunction "KL_1") (pintype "passive"))
    )
    (net (code "106") (name "Net-(X6D-KL)") (class "Default")
      (node (ref "C36") (pin "2") (pinfunction "2_2") (pintype "passive"))
      (node (ref "C37") (pin "2") (pinfunction "2_2") (pintype "passive"))
      (node (ref "L2") (pin "1") (pinfunction "1_1") (pintype "passive"))
      (node (ref "X6") (pin "2") (pinfunction "KL_2") (pintype "passive"))
    )
    (net (code "107") (name "Net-(X6E-KL)") (class "Default")
      (node (ref "C38") (pin "2") (pinfunction "2_2") (pintype "passive"))
      (node (ref "C39") (pin "2") (pinfunction "2_2") (pintype "passive"))
      (node (ref "L3") (pin "1") (pinfunction "1_1") (pintype "passive"))
      (node (ref "X6") (pin "3") (pinfunction "KL_3") (pintype "passive"))
    )
    (net (code "108") (name "unconnected-(R5-A-Pad1)") (class "Default")
      (node (ref "R5") (pin "1") (pinfunction "A_1") (pintype "passive"))
    )
    (net (code "109") (name "unconnected-(R6-A-Pad1)") (class "Default")
      (node (ref "R6") (pin "1") (pinfunction "A_1") (pintype "passive"))
    )
    (net (code "110") (name "unconnected-(R7-A-Pad1)") (class "Default")
      (node (ref "R7") (pin "1") (pinfunction "A_1") (pintype "passive"))
    )
    (net (code "111") (name "unconnected-(R14-A-Pad1)") (class "Default")
      (node (ref "R14") (pin "1") (pinfunction "A_1") (pintype "passive"))
    )
    (net (code "112") (name "unconnected-(R15-A-Pad1)") (class "Default")
      (node (ref "R15") (pin "1") (pinfunction "A_1") (pintype "passive"))
    )
    (net (code "113") (name "unconnected-(R16-A-Pad1)") (class "Default")
      (node (ref "R16") (pin "1") (pinfunction "A_1") (pintype "passive"))
    )
    (net (code "114") (name "unconnected-(SV2-Pad1)") (class "Default")
      (node (ref "SV2") (pin "1") (pinfunction "1_1") (pintype "passive"))
    )
    (net (code "115") (name "unconnected-(SV2-Pad3)") (class "Default")
      (node (ref "SV2") (pin "3") (pinfunction "3_3") (pintype "passive"))
    )
    (net (code "116") (name "unconnected-(SV2-Pad4)") (class "Default")
      (node (ref "SV2") (pin "4") (pinfunction "4_4") (pintype "passive"))
    )
    (net (code "117") (name "unconnected-(SV2-Pad5)") (class "Default")
      (node (ref "SV2") (pin "5") (pinfunction "5_5") (pintype "passive"))
    )
    (net (code "118") (name "unconnected-(SV2-Pad7)") (class "Default")
      (node (ref "SV2") (pin "7") (pinfunction "7_7") (pintype "passive"))
    )
    (net (code "119") (name "unconnected-(SV2-Pad8)") (class "Default")
      (node (ref "SV2") (pin "8") (pinfunction "8_8") (pintype "passive"))
    )
    (net (code "120") (name "unconnected-(SV2-Pad10)") (class "Default")
      (node (ref "SV2") (pin "10") (pinfunction "10_10") (pintype "passive"))
    )
    (net (code "121") (name "unconnected-(SV2-Pad11)") (class "Default")
      (node (ref "SV2") (pin "11") (pinfunction "11_11") (pintype "passive"))
    )
    (net (code "122") (name "unconnected-(SV2-Pad12)") (class "Default")
      (node (ref "SV2") (pin "12") (pinfunction "12_12") (pintype "passive"))
    )
    (net (code "123") (name "unconnected-(SV2-Pad13)") (class "Default")
      (node (ref "SV2") (pin "13") (pinfunction "13_13") (pintype "passive"))
    )
    (net (code "124") (name "unconnected-(SV2-Pad15)") (class "Default")
      (node (ref "SV2") (pin "15") (pinfunction "15_15") (pintype "passive"))
    )
    (net (code "125") (name "unconnected-(SV2-Pad16)") (class "Default")
      (node (ref "SV2") (pin "16") (pinfunction "16_16") (pintype "passive"))
    )
    (net (code "126") (name "unconnected-(SV2-Pad17)") (class "Default")
      (node (ref "SV2") (pin "17") (pinfunction "17_17") (pintype "passive"))
    )
    (net (code "127") (name "unconnected-(SV2-Pad18)") (class "Default")
      (node (ref "SV2") (pin "18") (pinfunction "18_18") (pintype "passive"))
    )
    (net (code "128") (name "unconnected-(SV2-Pad22)") (class "Default")
      (node (ref "SV2") (pin "22") (pinfunction "22_22") (pintype "passive"))
    )
    (net (code "129") (name "unconnected-(SV2-Pad24)") (class "Default")
      (node (ref "SV2") (pin "24") (pinfunction "24_24") (pintype "passive"))
    )
    (net (code "130") (name "unconnected-(SV2-Pad26)") (class "Default")
      (node (ref "SV2") (pin "26") (pinfunction "26_26") (pintype "passive"))
    )
    (net (code "131") (name "unconnected-(SV2-Pad27)") (class "Default")
      (node (ref "SV2") (pin "27") (pinfunction "27_27") (pintype "passive"))
    )
    (net (code "132") (name "unconnected-(SV2-Pad28)") (class "Default")
      (node (ref "SV2") (pin "28") (pinfunction "28_28") (pintype "passive"))
    )
    (net (code "133") (name "unconnected-(SV2-Pad29)") (class "Default")
      (node (ref "SV2") (pin "29") (pinfunction "29_29") (pintype "passive"))
    )
    (net (code "134") (name "unconnected-(SV2-Pad31)") (class "Default")
      (node (ref "SV2") (pin "31") (pinfunction "31_31") (pintype "passive"))
    )
    (net (code "135") (name "unconnected-(SV2-Pad32)") (class "Default")
      (node (ref "SV2") (pin "32") (pinfunction "32_32") (pintype "passive"))
    )
    (net (code "136") (name "unconnected-(SV2-Pad33)") (class "Default")
      (node (ref "SV2") (pin "33") (pinfunction "33_33") (pintype "passive"))
    )
    (net (code "137") (name "unconnected-(SV2-Pad35)") (class "Default")
      (node (ref "SV2") (pin "35") (pinfunction "35_35") (pintype "passive"))
    )
    (net (code "138") (name "unconnected-(SV2-Pad36)") (class "Default")
      (node (ref "SV2") (pin "36") (pinfunction "36_36") (pintype "passive"))
    )
    (net (code "139") (name "unconnected-(SV2-Pad37)") (class "Default")
      (node (ref "SV2") (pin "37") (pinfunction "37_37") (pintype "passive"))
    )
    (net (code "140") (name "unconnected-(SV2-Pad38)") (class "Default")
      (node (ref "SV2") (pin "38") (pinfunction "38_38") (pintype "passive"))
    )
    (net (code "141") (name "unconnected-(SV2-Pad40)") (class "Default")
      (node (ref "SV2") (pin "40") (pinfunction "40_40") (pintype "passive"))
    )
    (net (code "142") (name "unconnected-(U$1-CHANNEL_A-PadP12)") (class "Default")
      (node (ref "U$1") (pin "P12") (pinfunction "CHANNEL_A_P12") (pintype "bidirectional"))
    )
    (net (code "143") (name "unconnected-(U$1-CHANNEL_B-PadP16)") (class "Default")
      (node (ref "U$1") (pin "P16") (pinfunction "CHANNEL_B_P16") (pintype "bidirectional"))
    )
    (net (code "144") (name "unconnected-(U$1-~{CHANNEL_A\\}-PadP14)") (class "Default")
      (node (ref "U$1") (pin "P14") (pinfunction "~{CHANNEL_A\\}_P14") (pintype "bidirectional"))
    )
    (net (code "145") (name "unconnected-(U$1-~{CHANNEL_B\\}-PadP18)") (class "Default")
      (node (ref "U$1") (pin "P18") (pinfunction "~{CHANNEL_B\\}_P18") (pintype "bidirectional"))
    )
    (net (code "146") (name "unconnected-(U6-PGD-Pad3)") (class "Default")
      (node (ref "U6") (pin "3") (pinfunction "PGD_3") (pintype "bidirectional"))
    )
    (net (code "147") (name "unconnected-(X6F-KL-Pad4)") (class "Default")
      (node (ref "X6") (pin "4") (pinfunction "KL_4") (pintype "passive"))
    )
  )
)
